# 09_Misc.net
KiCad netlist of a schematic drawn in Altium Designer
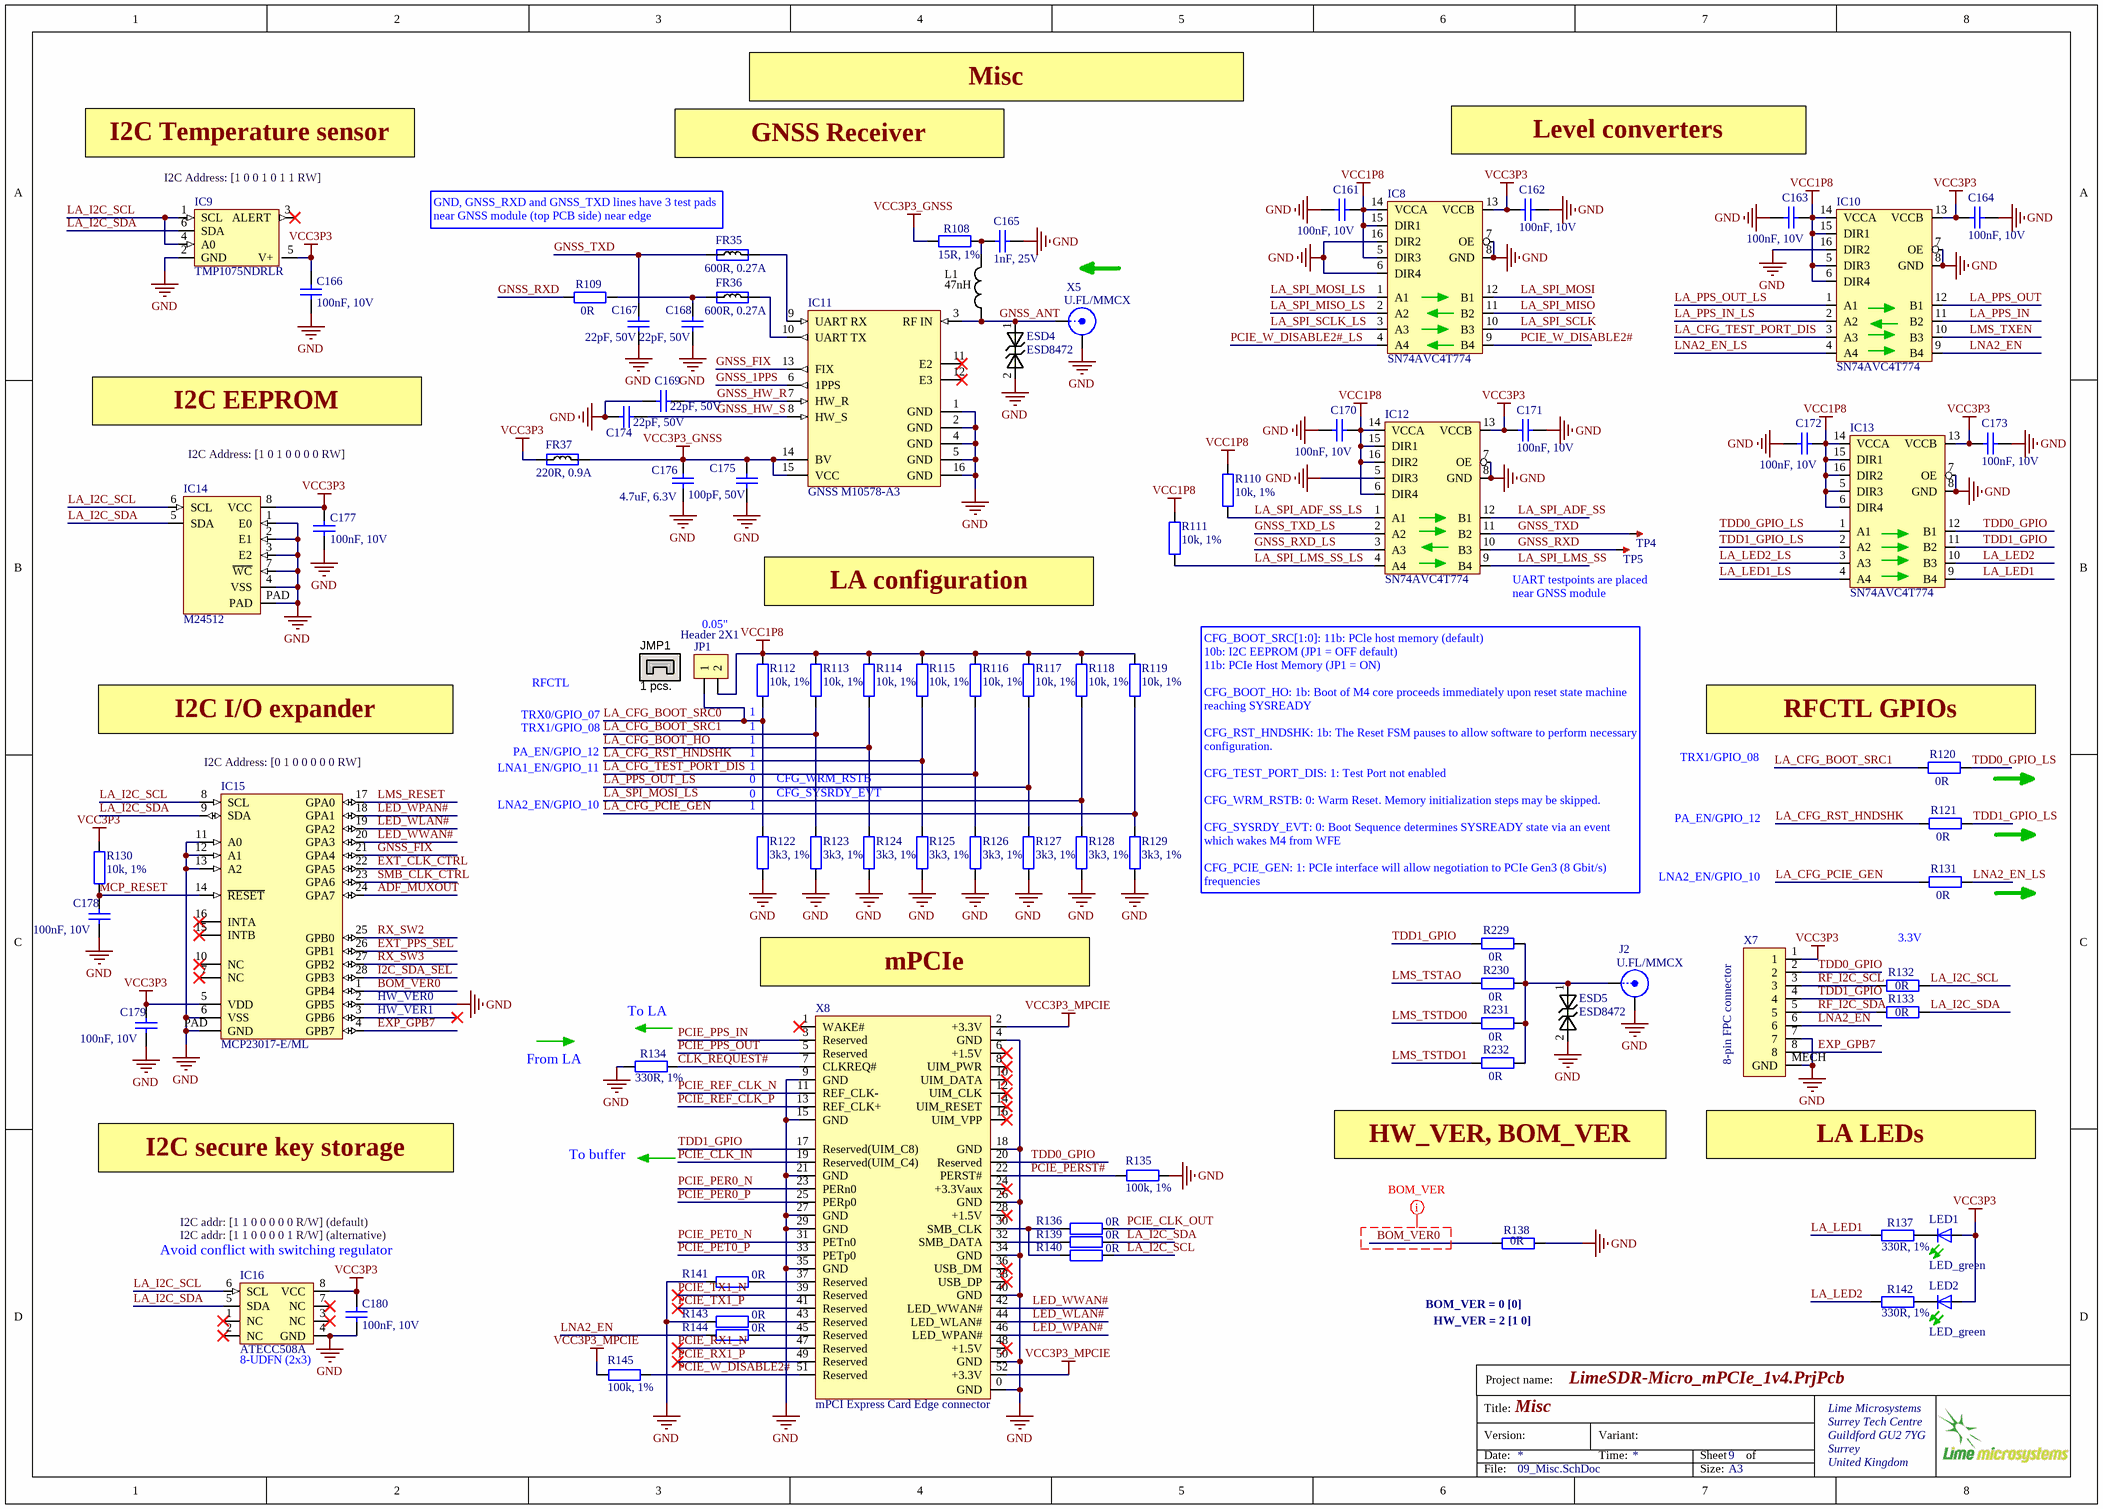
[diagram p0: 09_Misc.SchDoc]

(export (version "E")
  (design (tool "Eeschema 10.0.6"))
  (components
    (comp (ref "C161")
      (value "100nF, 10V")
      (footprint "CAP0201")
      (fields (field (name "MANUFACTURER") "Samsung") (field (name "TOLERANCE") "20%"))
      (libsource (lib "LimeMicroAltiumLib_schLib") (part "Cap_0402"))
    )
    (comp (ref "C162")
      (value "100nF, 10V")
      (footprint "CAP0201")
      (fields (field (name "MANUFACTURER") "Samsung") (field (name "TOLERANCE") "20%"))
      (libsource (lib "LimeMicroAltiumLib_schLib") (part "Cap_0402"))
    )
    (comp (ref "C163")
      (value "100nF, 10V")
      (footprint "CAP0201")
      (fields (field (name "MANUFACTURER") "Samsung") (field (name "TOLERANCE") "20%"))
      (libsource (lib "LimeMicroAltiumLib_schLib") (part "Cap_0402"))
    )
    (comp (ref "C164")
      (value "100nF, 10V")
      (footprint "CAP0201")
      (fields (field (name "MANUFACTURER") "Samsung") (field (name "TOLERANCE") "20%"))
      (libsource (lib "LimeMicroAltiumLib_schLib") (part "Cap_0402"))
    )
    (comp (ref "C165")
      (value "1nF, 25V")
      (footprint "CAP0201")
      (fields (field (name "TOLERANCE") "±10%") (field (name "MANUFACTURER") "TDK Corporation"))
      (libsource (lib "LimeMicroAltiumLib_schLib") (part "Cap_0402"))
    )
    (comp (ref "C166")
      (value "100nF, 10V")
      (footprint "CAP0201")
      (fields (field (name "MANUFACTURER") "Samsung") (field (name "TOLERANCE") "20%"))
      (libsource (lib "LimeMicroAltiumLib_schLib") (part "Cap_0402"))
    )
    (comp (ref "C167")
      (value "22pF, 50V")
      (footprint "CAP0201")
      (fields
        (field (name "MANUFACTURER") "Murata")
        (field (name "TOLERANCE") "5%")
        (field (name "VOLTAGE") "50V")
      )
      (libsource (lib "LimeMicroAltiumLib_schLib") (part "Cap_0402"))
    )
    (comp (ref "C168")
      (value "22pF, 50V")
      (footprint "CAP0201")
      (fields
        (field (name "MANUFACTURER") "Murata")
        (field (name "TOLERANCE") "5%")
        (field (name "VOLTAGE") "50V")
      )
      (libsource (lib "LimeMicroAltiumLib_schLib") (part "Cap_0402"))
    )
    (comp (ref "C169")
      (value "22pF, 50V")
      (footprint "CAP0201")
      (fields
        (field (name "MANUFACTURER") "Murata")
        (field (name "TOLERANCE") "5%")
        (field (name "VOLTAGE") "50V")
      )
      (libsource (lib "LimeMicroAltiumLib_schLib") (part "Cap_0402"))
    )
    (comp (ref "C170")
      (value "100nF, 10V")
      (footprint "CAP0201")
      (fields (field (name "MANUFACTURER") "Samsung") (field (name "TOLERANCE") "20%"))
      (libsource (lib "LimeMicroAltiumLib_schLib") (part "Cap_0402"))
    )
    (comp (ref "C171")
      (value "100nF, 10V")
      (footprint "CAP0201")
      (fields (field (name "MANUFACTURER") "Samsung") (field (name "TOLERANCE") "20%"))
      (libsource (lib "LimeMicroAltiumLib_schLib") (part "Cap_0402"))
    )
    (comp (ref "C172")
      (value "100nF, 10V")
      (footprint "CAP0201")
      (fields (field (name "MANUFACTURER") "Samsung") (field (name "TOLERANCE") "20%"))
      (libsource (lib "LimeMicroAltiumLib_schLib") (part "Cap_0402"))
    )
    (comp (ref "C173")
      (value "100nF, 10V")
      (footprint "CAP0201")
      (fields (field (name "MANUFACTURER") "Samsung") (field (name "TOLERANCE") "20%"))
      (libsource (lib "LimeMicroAltiumLib_schLib") (part "Cap_0402"))
    )
    (comp (ref "C174")
      (value "22pF, 50V")
      (footprint "CAP0201")
      (fields
        (field (name "MANUFACTURER") "Murata")
        (field (name "TOLERANCE") "5%")
        (field (name "VOLTAGE") "50V")
      )
      (libsource (lib "LimeMicroAltiumLib_schLib") (part "Cap_0402"))
    )
    (comp (ref "C175")
      (value "100pF, 50V")
      (footprint "CAP0201")
      (fields
        (field (name "MANUFACTURER") "TDK")
        (field (name "TOLERANCE") "5%")
        (field (name "VOLTAGE") "50V")
      )
      (libsource (lib "LimeMicroAltiumLib_schLib") (part "Cap_0402"))
    )
    (comp (ref "C176")
      (value "4.7uF, 6.3V")
      (footprint "CAP0402")
      (fields
        (field (name "MANUFACTURER") "Murata Electronics North America")
        (field (name "TOLERANCE") "±20%")
      )
      (libsource (lib "LimeMicroAltiumLib_schLib") (part "Cap_0402"))
    )
    (comp (ref "C177")
      (value "100nF, 10V")
      (footprint "CAP0201")
      (fields (field (name "MANUFACTURER") "Samsung") (field (name "TOLERANCE") "20%"))
      (libsource (lib "LimeMicroAltiumLib_schLib") (part "Cap_0402"))
    )
    (comp (ref "C178")
      (value "100nF, 10V")
      (footprint "CAP0201")
      (fields (field (name "MANUFACTURER") "Samsung") (field (name "TOLERANCE") "20%"))
      (libsource (lib "LimeMicroAltiumLib_schLib") (part "Cap_0402"))
    )
    (comp (ref "C179")
      (value "100nF, 10V")
      (footprint "CAP0201")
      (fields (field (name "MANUFACTURER") "Samsung") (field (name "TOLERANCE") "20%"))
      (libsource (lib "LimeMicroAltiumLib_schLib") (part "Cap_0402"))
    )
    (comp (ref "C180")
      (value "100nF, 10V")
      (footprint "CAP0201")
      (fields (field (name "MANUFACTURER") "Samsung") (field (name "TOLERANCE") "20%"))
      (libsource (lib "LimeMicroAltiumLib_schLib") (part "Cap_0402"))
    )
    (comp (ref "ESD4")
      (value "ESD8472")
      (footprint "ESD8472_X3DFN2")
      (fields (field (name "MANUFACTURER") "ON Semiconductor"))
      (libsource (lib "LimeMicroAltiumLib_schLib") (part "ESD8472"))
    )
    (comp (ref "ESD5")
      (value "ESD8472")
      (footprint "ESD8472_X3DFN2")
      (fields (field (name "MANUFACTURER") "ON Semiconductor"))
      (libsource (lib "LimeMicroAltiumLib_schLib") (part "ESD8472"))
    )
    (comp (ref "FR35")
      (value "600R, 0.27A")
      (footprint "RES0201")
      (fields (field (name "MANUFACTURER") "Taiyo Yuden"))
      (libsource (lib "LimeMicroAltiumLib_schLib") (part "Ferrite"))
    )
    (comp (ref "FR36")
      (value "600R, 0.27A")
      (footprint "RES0201")
      (fields (field (name "MANUFACTURER") "Taiyo Yuden"))
      (libsource (lib "LimeMicroAltiumLib_schLib") (part "Ferrite"))
    )
    (comp (ref "FR37")
      (value "220R, 0.9A")
      (footprint "RES0402")
      (fields (field (name "MANUFACTURER") "TDK Corporation"))
      (libsource (lib "LimeFPGAboard_schLib") (part "Ferrite"))
    )
    (comp (ref "IC8")
      (value "SN74AVC4T774")
      (footprint "SN74AVC4T774_v1")
      (fields (field (name "MANUFACTURER") "Texas Instruments"))
      (libsource (lib "LimeMicroAltiumLib") (part "SN74AVC4T774"))
    )
    (comp (ref "IC9")
      (value "TMP1075NDRLR")
      (footprint "TMP1075NDRLR_temperature_sensor_SOT563")
      (fields (field (name "MANUFACTURER") "Texas Instruments"))
      (libsource (lib "LimeMicroAltiumLib_schLib_r04") (part "TMP1075NDRLR_temperature_sensor"))
    )
    (comp (ref "IC10")
      (value "SN74AVC4T774")
      (footprint "SN74AVC4T774_v1")
      (fields (field (name "MANUFACTURER") "Texas Instruments"))
      (libsource (lib "LimeMicroAltiumLib") (part "SN74AVC4T774"))
    )
    (comp (ref "IC11")
      (value "GNSS M10578-A3")
      (footprint "M10578-A3_v2")
      (fields (field (name "MANUFACTURER") "Antenova"))
      (libsource (lib "LimeMicroAltiumLib_schLib_r04") (part "M10578-A3_GPS_GNSS"))
    )
    (comp (ref "IC12")
      (value "SN74AVC4T774")
      (footprint "SN74AVC4T774_v1")
      (fields (field (name "MANUFACTURER") "Texas Instruments"))
      (libsource (lib "LimeMicroAltiumLib") (part "SN74AVC4T774"))
    )
    (comp (ref "IC13")
      (value "SN74AVC4T774")
      (footprint "SN74AVC4T774_v1")
      (fields (field (name "MANUFACTURER") "Texas Instruments"))
      (libsource (lib "LimeMicroAltiumLib") (part "SN74AVC4T774"))
    )
    (comp (ref "IC14")
      (value "M24512")
      (footprint "M24128-DFMC6TG")
      (fields (field (name "MANUFACTURER") "STMicroelectronics"))
      (libsource (lib "LimeMicroAltiumLib_schLib") (part "M24128-DFMC6TG"))
    )
    (comp (ref "IC15")
      (value "MCP23017-E/ML")
      (footprint "MCP23017-E/ML_QFN28")
      (fields (field (name "MANUFACTURER") "Microchip"))
      (libsource (lib "LimeMicroAltiumLib") (part "MCP23017-E/ML_I2C_expander"))
    )
    (comp (ref "IC16")
      (value "ATECC508A")
      (footprint "LimeMicroAltiumLib:ATECC508A_UDFN8_v2")
      (fields (field (name "MANUFACTURER") "Microchip"))
      (libsource (lib "LimeMicroAltiumLib_schLib_r01") (part "ATECC508A_authentication_IC"))
    )
    (comp (ref "J2")
      (value "U.FL/MMCX")
      (footprint "MMCX_UFL_conn_u_v2")
      (description "CONN UMC RCPT STR 50 OHM SMD")
      (fields (field (name "MANUFACTURER") "Molex, LLC"))
      (libsource (lib "LimeMicroAltiumLib_schLib") (part "RF_IF_connector"))
    )
    (comp (ref "JMP1")
      (value "1 pcs.")
      (footprint "MECH_JUMPER_HALF_PITCH")
      (description "Shorting Jumper, 2-position, 1.27mm pitch")
      (fields (field (name "MANUFACTURER") "Sullins"))
      (libsource (lib "LimeMicroAltiumLib_schLib") (part "JUMP_2P_CONN_HEADER"))
    )
    (comp (ref "JP1")
      (value "Header 2X1")
      (footprint "HEADER_2x1_TH_HALF_PITCH")
      (fields (field (name "MANUFACTURER") "Harwin"))
      (libsource (lib "LimeMicroAltiumLib") (part "Header_2X1"))
    )
    (comp (ref "L1")
      (value "47nH")
      (footprint "RES0402")
      (fields
        (field (name "MANUFACTURER") "COILCRAFT")
        (field (name "MANUFACTURER PART NUMBER") "0402HP-47NXJLU")
      )
      (libsource (lib "LimeMicroAltiumLib_schLib") (part "Inductor_0603"))
    )
    (comp (ref "LED1")
      (value "LED_green")
      (footprint "LED0201")
      (fields (field (name "MANUFACTURER") "Kingbright"))
      (libsource (lib "LimeFPGAboard_schLib") (part "LED_green"))
    )
    (comp (ref "LED2")
      (value "LED_green")
      (footprint "LED0201")
      (fields (field (name "MANUFACTURER") "Kingbright"))
      (libsource (lib "LimeFPGAboard_schLib") (part "LED_green"))
    )
    (comp (ref "R108")
      (value "15R, 1%")
      (footprint "RES0201")
      (fields (field (name "MANUFACTURER") "Yageo") (field (name "TOLERANCE") "1%"))
      (libsource (lib "LimeFPGAboard_schLib") (part "Res_0402"))
    )
    (comp (ref "R109")
      (value "0R")
      (footprint "RES0201")
      (fields (field (name "MANUFACTURER") "Yageo") (field (name "TOLERANCE") "5%"))
      (libsource (lib "LimeFPGAboard_schLib") (part "Res_0402"))
    )
    (comp (ref "R110")
      (value "10k, 1%")
      (footprint "RES0201")
      (fields (field (name "MANUFACTURER") "Yageo") (field (name "TOLERANCE") "1%"))
      (libsource (lib "LimeFPGAboard_schLib") (part "Res_0402"))
    )
    (comp (ref "R111")
      (value "10k, 1%")
      (footprint "RES0201")
      (fields (field (name "MANUFACTURER") "Yageo") (field (name "TOLERANCE") "1%"))
      (libsource (lib "LimeFPGAboard_schLib") (part "Res_0402"))
    )
    (comp (ref "R112")
      (value "10k, 1%")
      (footprint "RES0201")
      (fields (field (name "MANUFACTURER") "Yageo") (field (name "TOLERANCE") "1%"))
      (libsource (lib "LimeFPGAboard_schLib") (part "Res_0402"))
    )
    (comp (ref "R113")
      (value "10k, 1%")
      (footprint "RES0201")
      (fields (field (name "MANUFACTURER") "Yageo") (field (name "TOLERANCE") "1%"))
      (libsource (lib "LimeFPGAboard_schLib") (part "Res_0402"))
    )
    (comp (ref "R114")
      (value "10k, 1%")
      (footprint "RES0201")
      (fields (field (name "MANUFACTURER") "Yageo") (field (name "TOLERANCE") "1%"))
      (libsource (lib "LimeFPGAboard_schLib") (part "Res_0402"))
    )
    (comp (ref "R115")
      (value "10k, 1%")
      (footprint "RES0201")
      (fields (field (name "MANUFACTURER") "Yageo") (field (name "TOLERANCE") "1%"))
      (libsource (lib "LimeFPGAboard_schLib") (part "Res_0402"))
    )
    (comp (ref "R116")
      (value "10k, 1%")
      (footprint "RES0201")
      (fields (field (name "MANUFACTURER") "Yageo") (field (name "TOLERANCE") "1%"))
      (libsource (lib "LimeFPGAboard_schLib") (part "Res_0402"))
    )
    (comp (ref "R117")
      (value "10k, 1%")
      (footprint "RES0201")
      (fields (field (name "MANUFACTURER") "Yageo") (field (name "TOLERANCE") "1%"))
      (libsource (lib "LimeFPGAboard_schLib") (part "Res_0402"))
    )
    (comp (ref "R118")
      (value "10k, 1%")
      (footprint "RES0201")
      (fields (field (name "MANUFACTURER") "Yageo") (field (name "TOLERANCE") "1%"))
      (libsource (lib "LimeFPGAboard_schLib") (part "Res_0402"))
    )
    (comp (ref "R119")
      (value "10k, 1%")
      (footprint "RES0201")
      (fields (field (name "MANUFACTURER") "Yageo") (field (name "TOLERANCE") "1%"))
      (libsource (lib "LimeFPGAboard_schLib") (part "Res_0402"))
    )
    (comp (ref "R120")
      (value "0R")
      (footprint "RES0201")
      (fields (field (name "MANUFACTURER") "Yageo") (field (name "TOLERANCE") "5%"))
      (libsource (lib "LimeFPGAboard_schLib") (part "Res_0402"))
    )
    (comp (ref "R121")
      (value "0R")
      (footprint "RES0201")
      (fields (field (name "MANUFACTURER") "Yageo") (field (name "TOLERANCE") "5%"))
      (libsource (lib "LimeFPGAboard_schLib") (part "Res_0402"))
    )
    (comp (ref "R122")
      (value "3k3, 1%")
      (footprint "RES0201")
      (fields (field (name "MANUFACTURER") "Yageo") (field (name "TOLERANCE") "1%"))
      (libsource (lib "LimeFPGAboard_schLib") (part "Res_0402"))
    )
    (comp (ref "R123")
      (value "3k3, 1%")
      (footprint "RES0201")
      (fields (field (name "MANUFACTURER") "Yageo") (field (name "TOLERANCE") "1%"))
      (libsource (lib "LimeFPGAboard_schLib") (part "Res_0402"))
    )
    (comp (ref "R124")
      (value "3k3, 1%")
      (footprint "RES0201")
      (fields (field (name "MANUFACTURER") "Yageo") (field (name "TOLERANCE") "1%"))
      (libsource (lib "LimeFPGAboard_schLib") (part "Res_0402"))
    )
    (comp (ref "R125")
      (value "3k3, 1%")
      (footprint "RES0201")
      (fields (field (name "MANUFACTURER") "Yageo") (field (name "TOLERANCE") "1%"))
      (libsource (lib "LimeFPGAboard_schLib") (part "Res_0402"))
    )
    (comp (ref "R126")
      (value "3k3, 1%")
      (footprint "RES0201")
      (fields (field (name "MANUFACTURER") "Yageo") (field (name "TOLERANCE") "1%"))
      (libsource (lib "LimeFPGAboard_schLib") (part "Res_0402"))
    )
    (comp (ref "R127")
      (value "3k3, 1%")
      (footprint "RES0201")
      (fields (field (name "MANUFACTURER") "Yageo") (field (name "TOLERANCE") "1%"))
      (libsource (lib "LimeFPGAboard_schLib") (part "Res_0402"))
    )
    (comp (ref "R128")
      (value "3k3, 1%")
      (footprint "RES0201")
      (fields (field (name "MANUFACTURER") "Yageo") (field (name "TOLERANCE") "1%"))
      (libsource (lib "LimeFPGAboard_schLib") (part "Res_0402"))
    )
    (comp (ref "R129")
      (value "3k3, 1%")
      (footprint "RES0201")
      (fields (field (name "MANUFACTURER") "Yageo") (field (name "TOLERANCE") "1%"))
      (libsource (lib "LimeFPGAboard_schLib") (part "Res_0402"))
    )
    (comp (ref "R130")
      (value "10k, 1%")
      (footprint "RES0201")
      (fields (field (name "MANUFACTURER") "Yageo") (field (name "TOLERANCE") "1%"))
      (libsource (lib "LimeFPGAboard_schLib") (part "Res_0402"))
    )
    (comp (ref "R131")
      (value "0R")
      (footprint "RES0201")
      (fields (field (name "MANUFACTURER") "Yageo") (field (name "TOLERANCE") "5%"))
      (libsource (lib "LimeFPGAboard_schLib") (part "Res_0402"))
    )
    (comp (ref "R132")
      (value "0R")
      (footprint "RES0201")
      (fields (field (name "MANUFACTURER") "Yageo") (field (name "TOLERANCE") "5%"))
      (libsource (lib "LimeFPGAboard_schLib") (part "Res_0402"))
    )
    (comp (ref "R133")
      (value "0R")
      (footprint "RES0201")
      (fields (field (name "MANUFACTURER") "Yageo") (field (name "TOLERANCE") "5%"))
      (libsource (lib "LimeFPGAboard_schLib") (part "Res_0402"))
    )
    (comp (ref "R134")
      (value "330R, 1%")
      (footprint "RES0201")
      (fields (field (name "MANUFACTURER") "Vishay Dale") (field (name "TOLERANCE") "1%"))
      (libsource (lib "LimeFPGAboard_schLib") (part "Res_0402"))
    )
    (comp (ref "R135")
      (value "100k, 1%")
      (footprint "RES0201")
      (fields (field (name "MANUFACTURER") "Yageo") (field (name "TOLERANCE") "1%"))
      (libsource (lib "LimeMicroAltiumLib_schLib") (part "Res_0402"))
    )
    (comp (ref "R136")
      (value "0R")
      (footprint "RES0201")
      (fields (field (name "MANUFACTURER") "Yageo") (field (name "TOLERANCE") "5%"))
      (libsource (lib "LimeFPGAboard_schLib") (part "Res_0402"))
    )
    (comp (ref "R137")
      (value "330R, 1%")
      (footprint "RES0201")
      (fields (field (name "MANUFACTURER") "Vishay Dale") (field (name "TOLERANCE") "1%"))
      (libsource (lib "LimeFPGAboard_schLib") (part "Res_0402"))
    )
    (comp (ref "R138")
      (value "0R")
      (footprint "RES0201")
      (fields (field (name "MANUFACTURER") "Yageo") (field (name "TOLERANCE") "5%"))
      (libsource (lib "LimeFPGAboard_schLib") (part "Res_0402"))
    )
    (comp (ref "R139")
      (value "0R")
      (footprint "RES0201")
      (fields (field (name "MANUFACTURER") "Yageo") (field (name "TOLERANCE") "5%"))
      (libsource (lib "LimeFPGAboard_schLib") (part "Res_0402"))
    )
    (comp (ref "R140")
      (value "0R")
      (footprint "RES0201")
      (fields (field (name "MANUFACTURER") "Yageo") (field (name "TOLERANCE") "5%"))
      (libsource (lib "LimeFPGAboard_schLib") (part "Res_0402"))
    )
    (comp (ref "R141")
      (value "0R")
      (footprint "RES0201")
      (fields (field (name "MANUFACTURER") "Yageo") (field (name "TOLERANCE") "5%"))
      (libsource (lib "LimeFPGAboard_schLib") (part "Res_0402"))
    )
    (comp (ref "R142")
      (value "330R, 1%")
      (footprint "RES0201")
      (fields (field (name "MANUFACTURER") "Vishay Dale") (field (name "TOLERANCE") "1%"))
      (libsource (lib "LimeFPGAboard_schLib") (part "Res_0402"))
    )
    (comp (ref "R143")
      (value "0R")
      (footprint "RES0201")
      (fields (field (name "MANUFACTURER") "Yageo") (field (name "TOLERANCE") "5%"))
      (libsource (lib "LimeFPGAboard_schLib") (part "Res_0402"))
    )
    (comp (ref "R144")
      (value "0R")
      (footprint "RES0201")
      (fields (field (name "MANUFACTURER") "Yageo") (field (name "TOLERANCE") "5%"))
      (libsource (lib "LimeFPGAboard_schLib") (part "Res_0402"))
    )
    (comp (ref "R145")
      (value "100k, 1%")
      (footprint "RES0201")
      (fields (field (name "MANUFACTURER") "Yageo") (field (name "TOLERANCE") "1%"))
      (libsource (lib "LimeMicroAltiumLib_schLib") (part "Res_0402"))
    )
    (comp (ref "R229")
      (value "0R")
      (footprint "RES0201")
      (fields (field (name "MANUFACTURER") "Yageo") (field (name "TOLERANCE") "5%"))
      (libsource (lib "LimeFPGAboard_schLib") (part "Res_0402"))
    )
    (comp (ref "R230")
      (value "0R")
      (footprint "RES0201")
      (fields (field (name "MANUFACTURER") "Yageo") (field (name "TOLERANCE") "5%"))
      (libsource (lib "LimeFPGAboard_schLib") (part "Res_0402"))
    )
    (comp (ref "R231")
      (value "0R")
      (footprint "RES0201")
      (fields (field (name "MANUFACTURER") "Yageo") (field (name "TOLERANCE") "5%"))
      (libsource (lib "LimeFPGAboard_schLib") (part "Res_0402"))
    )
    (comp (ref "R232")
      (value "0R")
      (footprint "RES0201")
      (fields (field (name "MANUFACTURER") "Yageo") (field (name "TOLERANCE") "5%"))
      (libsource (lib "LimeFPGAboard_schLib") (part "Res_0402"))
    )
    (comp (ref "TP4")
      (value "TESTPOINT_PAD")
      (footprint "TP_PAD_1MM")
      (description "Test Point PCB mount Miniature White")
      (libsource (lib "LimeMicroAltiumLib_schLib_r04") (part "TESTPOINT_PAD"))
    )
    (comp (ref "TP5")
      (value "TESTPOINT_PAD")
      (footprint "TP_PAD_1MM")
      (description "Test Point PCB mount Miniature White")
      (libsource (lib "LimeMicroAltiumLib_schLib_r04") (part "TESTPOINT_PAD"))
    )
    (comp (ref "X5")
      (value "U.FL/MMCX")
      (footprint "MMCX_UFL_conn_u_v2")
      (description "CONN UMC RCPT STR 50 OHM SMD")
      (fields (field (name "MANUFACTURER") "Molex, LLC"))
      (libsource (lib "LimeMicroAltiumLib_schLib") (part "RF_IF_connector"))
    )
    (comp (ref "X7")
      (value "8-pin FPC connector")
      (footprint "503480-0800_8PIN_FPC_CONN")
      (fields (field (name "MANUFACTURER") "Molex"))
      (libsource (lib "LimeMicroAltiumLib_schLib_r04") (part "503480-0800_8PIN_FPC_CONN"))
    )
    (comp (ref "X8")
      (value "mPCI Express Card Edge connector")
      (footprint "PCIe_MiniCard")
      (description "PCIe MiniCard full or half size")
      (libsource (lib "LimeMicroAltiumLib_schLib_r04") (part "PCIe_MiniCard_fingers"))
    )
  )
  (nets
    (net (code "1") (name "/ADF_MUXOUT") (class "Default")
      (node (ref "IC15") (pin "24") (pinfunction "GPA7_24") (pintype "bidirectional"))
    )
    (net (code "2") (name "/BOM_VER0") (class "Default")
      (node (ref "IC15") (pin "1") (pinfunction "GPB4_1") (pintype "bidirectional"))
      (node (ref "R138") (pin "1") (pinfunction "1_1") (pintype "passive"))
    )
    (net (code "3") (name "/CLK_REQUEST#") (class "Default")
      (node (ref "R134") (pin "1") (pinfunction "1_1") (pintype "passive"))
      (node (ref "X8") (pin "7") (pinfunction "CLKREQ#_7") (pintype "passive"))
    )
    (net (code "4") (name "/EXP_GPB7") (class "Default")
      (node (ref "IC15") (pin "4") (pinfunction "GPB7_4") (pintype "bidirectional"))
      (node (ref "X7") (pin "8") (pinfunction "8_8") (pintype "passive"))
    )
    (net (code "5") (name "/EXT_CLK_CTRL") (class "Default")
      (node (ref "IC15") (pin "22") (pinfunction "GPA5_22") (pintype "bidirectional"))
    )
    (net (code "6") (name "/EXT_PPS_SEL") (class "Default")
      (node (ref "IC15") (pin "26") (pinfunction "GPB1_26") (pintype "bidirectional"))
    )
    (net (code "7") (name "/GNSS_1PPS") (class "Default")
      (node (ref "IC11") (pin "6") (pinfunction "1PPS_6") (pintype "output"))
    )
    (net (code "8") (name "/GNSS_ANT") (class "Default")
      (node (ref "ESD4") (pin "1") (pinfunction "1_1") (pintype "passive"))
      (node (ref "IC11") (pin "3") (pinfunction "RF_IN_3") (pintype "input"))
      (node (ref "L1") (pin "1") (pinfunction "1_1") (pintype "passive"))
      (node (ref "X5") (pin "1") (pinfunction "X_1") (pintype "passive"))
    )
    (net (code "9") (name "/GNSS_FIX") (class "Default")
      (node (ref "IC11") (pin "13") (pinfunction "FIX_13") (pintype "output"))
      (node (ref "IC15") (pin "21") (pinfunction "GPA4_21") (pintype "bidirectional"))
    )
    (net (code "10") (name "/GNSS_HW_R") (class "Default")
      (node (ref "C169") (pin "1") (pinfunction "1_1") (pintype "passive"))
      (node (ref "IC11") (pin "7") (pinfunction "HW_R_7") (pintype "input"))
    )
    (net (code "11") (name "/GNSS_HW_S") (class "Default")
      (node (ref "C174") (pin "1") (pinfunction "1_1") (pintype "passive"))
      (node (ref "IC11") (pin "8") (pinfunction "HW_S_8") (pintype "input"))
    )
    (net (code "12") (name "/GNSS_RXD") (class "Default")
      (node (ref "IC12") (pin "10") (pinfunction "B3_10") (pintype "passive"))
      (node (ref "R109") (pin "1") (pinfunction "1_1") (pintype "passive"))
      (node (ref "TP5") (pin "1") (pintype "passive"))
    )
    (net (code "13") (name "/GNSS_RXD_LS") (class "Default")
      (node (ref "IC12") (pin "3") (pinfunction "A3_3") (pintype "passive"))
    )
    (net (code "14") (name "/GNSS_TXD") (class "Default")
      (node (ref "C167") (pin "1") (pinfunction "1_1") (pintype "passive"))
      (node (ref "FR35") (pin "1") (pinfunction "1_1") (pintype "passive"))
      (node (ref "IC12") (pin "11") (pinfunction "B2_11") (pintype "passive"))
      (node (ref "TP4") (pin "1") (pintype "passive"))
    )
    (net (code "15") (name "/GNSS_TXD_LS") (class "Default")
      (node (ref "IC12") (pin "2") (pinfunction "A2_2") (pintype "passive"))
    )
    (net (code "16") (name "/I2C_SDA_SEL") (class "Default")
      (node (ref "IC15") (pin "28") (pinfunction "GPB3_28") (pintype "bidirectional"))
    )
    (net (code "17") (name "/LA_CFG_BOOT_HO") (class "Default")
      (node (ref "R114") (pin "2") (pinfunction "2_2") (pintype "passive"))
      (node (ref "R124") (pin "1") (pinfunction "1_1") (pintype "passive"))
    )
    (net (code "18") (name "/LA_CFG_BOOT_SRC0") (class "Default")
      (node (ref "JP1") (pin "1") (pinfunction "1_1") (pintype "passive"))
      (node (ref "R112") (pin "2") (pinfunction "2_2") (pintype "passive"))
      (node (ref "R122") (pin "1") (pinfunction "1_1") (pintype "passive"))
    )
    (net (code "19") (name "/LA_CFG_BOOT_SRC1") (class "Default")
      (node (ref "R113") (pin "2") (pinfunction "2_2") (pintype "passive"))
      (node (ref "R120") (pin "1") (pinfunction "1_1") (pintype "passive"))
      (node (ref "R123") (pin "1") (pinfunction "1_1") (pintype "passive"))
    )
    (net (code "20") (name "/LA_CFG_PCIE_GEN") (class "Default")
      (node (ref "R119") (pin "2") (pinfunction "2_2") (pintype "passive"))
      (node (ref "R129") (pin "1") (pinfunction "1_1") (pintype "passive"))
      (node (ref "R131") (pin "1") (pinfunction "1_1") (pintype "passive"))
    )
    (net (code "21") (name "/LA_CFG_RST_HNDSHK") (class "Default")
      (node (ref "R115") (pin "2") (pinfunction "2_2") (pintype "passive"))
      (node (ref "R121") (pin "1") (pinfunction "1_1") (pintype "passive"))
      (node (ref "R125") (pin "1") (pinfunction "1_1") (pintype "passive"))
    )
    (net (code "22") (name "/LA_CFG_TEST_PORT_DIS") (class "Default")
      (node (ref "IC10") (pin "3") (pinfunction "A3_3") (pintype "passive"))
      (node (ref "R116") (pin "2") (pinfunction "2_2") (pintype "passive"))
      (node (ref "R126") (pin "1") (pinfunction "1_1") (pintype "passive"))
    )
    (net (code "23") (name "/LA_I2C_SCL") (class "Default")
      (node (ref "IC14") (pin "6") (pinfunction "SCL_6") (pintype "input"))
      (node (ref "IC15") (pin "8") (pinfunction "SCL_8") (pintype "input"))
      (node (ref "IC16") (pin "6") (pinfunction "SCL_6") (pintype "input"))
      (node (ref "IC9") (pin "1") (pinfunction "SCL_1") (pintype "input"))
      (node (ref "IC9") (pin "4") (pinfunction "A0_4") (pintype "input"))
      (node (ref "R132") (pin "2") (pinfunction "2_2") (pintype "passive"))
      (node (ref "R140") (pin "2") (pinfunction "2_2") (pintype "passive"))
    )
    (net (code "24") (name "/LA_I2C_SDA") (class "Default")
      (node (ref "IC14") (pin "5") (pinfunction "SDA_5") (pintype "bidirectional"))
      (node (ref "IC15") (pin "9") (pinfunction "SDA_9") (pintype "bidirectional"))
      (node (ref "IC16") (pin "5") (pinfunction "SDA_5") (pintype "bidirectional"))
      (node (ref "IC9") (pin "6") (pinfunction "SDA_6") (pintype "bidirectional"))
      (node (ref "R133") (pin "2") (pinfunction "2_2") (pintype "passive"))
      (node (ref "R139") (pin "2") (pinfunction "2_2") (pintype "passive"))
    )
    (net (code "25") (name "/LA_LED1") (class "Default")
      (node (ref "IC13") (pin "9") (pinfunction "B4_9") (pintype "passive"))
      (node (ref "R137") (pin "2") (pinfunction "2_2") (pintype "passive"))
    )
    (net (code "26") (name "/LA_LED1_LS") (class "Default")
      (node (ref "IC13") (pin "4") (pinfunction "A4_4") (pintype "passive"))
    )
    (net (code "27") (name "/LA_LED2") (class "Default")
      (node (ref "IC13") (pin "10") (pinfunction "B3_10") (pintype "passive"))
      (node (ref "R142") (pin "2") (pinfunction "2_2") (pintype "passive"))
    )
    (net (code "28") (name "/LA_LED2_LS") (class "Default")
      (node (ref "IC13") (pin "3") (pinfunction "A3_3") (pintype "passive"))
    )
    (net (code "29") (name "/LA_PPS_IN") (class "Default")
      (node (ref "IC10") (pin "11") (pinfunction "B2_11") (pintype "passive"))
    )
    (net (code "30") (name "/LA_PPS_IN_LS") (class "Default")
      (node (ref "IC10") (pin "2") (pinfunction "A2_2") (pintype "passive"))
    )
    (net (code "31") (name "/LA_PPS_OUT") (class "Default")
      (node (ref "IC10") (pin "12") (pinfunction "B1_12") (pintype "passive"))
    )
    (net (code "32") (name "/LA_PPS_OUT_LS") (class "Default")
      (node (ref "IC10") (pin "1") (pinfunction "A1_1") (pintype "passive"))
      (node (ref "R117") (pin "2") (pinfunction "2_2") (pintype "passive"))
      (node (ref "R127") (pin "1") (pinfunction "1_1") (pintype "passive"))
    )
    (net (code "33") (name "/LA_SPI_ADF_SS") (class "Default")
      (node (ref "IC12") (pin "12") (pinfunction "B1_12") (pintype "passive"))
    )
    (net (code "34") (name "/LA_SPI_ADF_SS_LS") (class "Default")
      (node (ref "IC12") (pin "1") (pinfunction "A1_1") (pintype "passive"))
      (node (ref "R110") (pin "2") (pinfunction "2_2") (pintype "passive"))
    )
    (net (code "35") (name "/LA_SPI_LMS_SS") (class "Default")
      (node (ref "IC12") (pin "9") (pinfunction "B4_9") (pintype "passive"))
    )
    (net (code "36") (name "/LA_SPI_LMS_SS_LS") (class "Default")
      (node (ref "IC12") (pin "4") (pinfunction "A4_4") (pintype "passive"))
      (node (ref "R111") (pin "2") (pinfunction "2_2") (pintype "passive"))
    )
    (net (code "37") (name "/LA_SPI_MISO") (class "Default")
      (node (ref "IC8") (pin "11") (pinfunction "B2_11") (pintype "passive"))
    )
    (net (code "38") (name "/LA_SPI_MISO_LS") (class "Default")
      (node (ref "IC8") (pin "2") (pinfunction "A2_2") (pintype "passive"))
    )
    (net (code "39") (name "/LA_SPI_MOSI") (class "Default")
      (node (ref "IC8") (pin "12") (pinfunction "B1_12") (pintype "passive"))
    )
    (net (code "40") (name "/LA_SPI_MOSI_LS") (class "Default")
      (node (ref "IC8") (pin "1") (pinfunction "A1_1") (pintype "passive"))
      (node (ref "R118") (pin "2") (pinfunction "2_2") (pintype "passive"))
      (node (ref "R128") (pin "1") (pinfunction "1_1") (pintype "passive"))
    )
    (net (code "41") (name "/LA_SPI_SCLK") (class "Default")
      (node (ref "IC8") (pin "10") (pinfunction "B3_10") (pintype "passive"))
    )
    (net (code "42") (name "/LA_SPI_SCLK_LS") (class "Default")
      (node (ref "IC8") (pin "3") (pinfunction "A3_3") (pintype "passive"))
    )
    (net (code "43") (name "/LED_WLAN#") (class "Default")
      (node (ref "IC15") (pin "19") (pinfunction "GPA2_19") (pintype "bidirectional"))
      (node (ref "X8") (pin "44") (pinfunction "LED_WLAN#_44") (pintype "passive"))
    )
    (net (code "44") (name "/LED_WPAN#") (class "Default")
      (node (ref "IC15") (pin "18") (pinfunction "GPA1_18") (pintype "bidirectional"))
      (node (ref "X8") (pin "46") (pinfunction "LED_WPAN#_46") (pintype "passive"))
    )
    (net (code "45") (name "/LED_WWAN#") (class "Default")
      (node (ref "IC15") (pin "20") (pinfunction "GPA3_20") (pintype "bidirectional"))
      (node (ref "X8") (pin "42") (pinfunction "LED_WWAN#_42") (pintype "passive"))
    )
    (net (code "46") (name "/LMS_RESET") (class "Default")
      (node (ref "IC15") (pin "17") (pinfunction "GPA0_17") (pintype "bidirectional"))
    )
    (net (code "47") (name "/LMS_TSTAO") (class "Default")
      (node (ref "R230") (pin "1") (pinfunction "1_1") (pintype "passive"))
    )
    (net (code "48") (name "/LMS_TSTDO0") (class "Default")
      (node (ref "R231") (pin "1") (pinfunction "1_1") (pintype "passive"))
    )
    (net (code "49") (name "/LMS_TSTDO1") (class "Default")
      (node (ref "R232") (pin "1") (pinfunction "1_1") (pintype "passive"))
    )
    (net (code "50") (name "/LMS_TXEN") (class "Default")
      (node (ref "IC10") (pin "10") (pinfunction "B3_10") (pintype "passive"))
    )
    (net (code "51") (name "/LNA2_EN") (class "Default")
      (node (ref "IC10") (pin "9") (pinfunction "B4_9") (pintype "passive"))
      (node (ref "R144") (pin "1") (pinfunction "1_1") (pintype "passive"))
      (node (ref "X7") (pin "6") (pinfunction "6_6") (pintype "passive"))
    )
    (net (code "52") (name "/LNA2_EN_LS") (class "Default")
      (node (ref "IC10") (pin "4") (pinfunction "A4_4") (pintype "passive"))
      (node (ref "R131") (pin "2") (pinfunction "2_2") (pintype "passive"))
    )
    (net (code "53") (name "/MCP_RESET") (class "Default")
      (node (ref "C178") (pin "1") (pinfunction "1_1") (pintype "passive"))
      (node (ref "IC15") (pin "14") (pinfunction "~{RESET}_14") (pintype "input"))
      (node (ref "R130") (pin "2") (pinfunction "2_2") (pintype "passive"))
    )
    (net (code "54") (name "/PCIE_CLK_IN") (class "Default")
      (node (ref "X8") (pin "19") (pinfunction "Reserved(UIM_C4)_19") (pintype "passive"))
    )
    (net (code "55") (name "/PCIE_CLK_OUT") (class "Default")
      (node (ref "R136") (pin "2") (pinfunction "2_2") (pintype "passive"))
    )
    (net (code "56") (name "/PCIE_PER0_N") (class "Default")
      (node (ref "X8") (pin "23") (pinfunction "PERn0_23") (pintype "passive"))
    )
    (net (code "57") (name "/PCIE_PER0_P") (class "Default")
      (node (ref "X8") (pin "25") (pinfunction "PERp0_25") (pintype "passive"))
    )
    (net (code "58") (name "/PCIE_PERST#") (class "Default")
      (node (ref "R135") (pin "2") (pinfunction "2_2") (pintype "passive"))
      (node (ref "X8") (pin "22") (pinfunction "PERST#_22") (pintype "passive"))
    )
    (net (code "59") (name "/PCIE_PET0_N") (class "Default")
      (node (ref "X8") (pin "31") (pinfunction "PETn0_31") (pintype "passive"))
    )
    (net (code "60") (name "/PCIE_PET0_P") (class "Default")
      (node (ref "X8") (pin "33") (pinfunction "PETp0_33") (pintype "passive"))
    )
    (net (code "61") (name "/PCIE_PPS_IN") (class "Default")
      (node (ref "X8") (pin "3") (pinfunction "Reserved_3") (pintype "passive"))
    )
    (net (code "62") (name "/PCIE_PPS_OUT") (class "Default")
      (node (ref "X8") (pin "5") (pinfunction "Reserved_5") (pintype "passive"))
    )
    (net (code "63") (name "/PCIE_REF_CLK_N") (class "Default")
      (node (ref "X8") (pin "11") (pinfunction "REF_CLK-_11") (pintype "passive"))
    )
    (net (code "64") (name "/PCIE_REF_CLK_P") (class "Default")
      (node (ref "X8") (pin "13") (pinfunction "REF_CLK+_13") (pintype "passive"))
    )
    (net (code "65") (name "/PCIE_RX1_N") (class "Default")
      (node (ref "X8") (pin "47") (pinfunction "Reserved_47") (pintype "passive+no_connect"))
    )
    (net (code "66") (name "/PCIE_RX1_P") (class "Default")
      (node (ref "X8") (pin "49") (pinfunction "Reserved_49") (pintype "passive+no_connect"))
    )
    (net (code "67") (name "/PCIE_TX1_N") (class "Default")
      (node (ref "X8") (pin "39") (pinfunction "Reserved_39") (pintype "passive+no_connect"))
    )
    (net (code "68") (name "/PCIE_TX1_P") (class "Default")
      (node (ref "X8") (pin "41") (pinfunction "Reserved_41") (pintype "passive+no_connect"))
    )
    (net (code "69") (name "/PCIE_W_DISABLE2#") (class "Default")
      (node (ref "IC8") (pin "9") (pinfunction "B4_9") (pintype "passive"))
      (node (ref "R145") (pin "1") (pinfunction "1_1") (pintype "passive"))
      (node (ref "X8") (pin "51") (pinfunction "Reserved_51") (pintype "passive"))
    )
    (net (code "70") (name "/PCIE_W_DISABLE2#_LS") (class "Default")
      (node (ref "IC8") (pin "4") (pinfunction "A4_4") (pintype "passive"))
    )
    (net (code "71") (name "/RF_I2C_SCL") (class "Default")
      (node (ref "R132") (pin "1") (pinfunction "1_1") (pintype "passive"))
      (node (ref "X7") (pin "3") (pinfunction "3_3") (pintype "passive"))
    )
    (net (code "72") (name "/RF_I2C_SDA") (class "Default")
      (node (ref "R133") (pin "1") (pinfunction "1_1") (pintype "passive"))
      (node (ref "X7") (pin "5") (pinfunction "5_5") (pintype "passive"))
    )
    (net (code "73") (name "/RX_SW2") (class "Default")
      (node (ref "IC15") (pin "25") (pinfunction "GPB0_25") (pintype "bidirectional"))
    )
    (net (code "74") (name "/RX_SW3") (class "Default")
      (node (ref "IC15") (pin "27") (pinfunction "GPB2_27") (pintype "bidirectional"))
    )
    (net (code "75") (name "/SMB_CLK_CTRL") (class "Default")
      (node (ref "IC15") (pin "23") (pinfunction "GPA6_23") (pintype "bidirectional"))
    )
    (net (code "76") (name "/TDD0_GPIO") (class "Default")
      (node (ref "IC13") (pin "12") (pinfunction "B1_12") (pintype "passive"))
      (node (ref "X7") (pin "2") (pinfunction "2_2") (pintype "passive"))
      (node (ref "X8") (pin "20") (pinfunction "Reserved_20") (pintype "passive"))
    )
    (net (code "77") (name "/TDD0_GPIO_LS") (class "Default")
      (node (ref "IC13") (pin "1") (pinfunction "A1_1") (pintype "passive"))
      (node (ref "R120") (pin "2") (pinfunction "2_2") (pintype "passive"))
    )
    (net (code "78") (name "/TDD1_GPIO") (class "Default")
      (node (ref "IC13") (pin "11") (pinfunction "B2_11") (pintype "passive"))
      (node (ref "R229") (pin "1") (pinfunction "1_1") (pintype "passive"))
      (node (ref "X7") (pin "4") (pinfunction "4_4") (pintype "passive"))
      (node (ref "X8") (pin "17") (pinfunction "Reserved(UIM_C8)_17") (pintype "passive"))
    )
    (net (code "79") (name "/TDD1_GPIO_LS") (class "Default")
      (node (ref "IC13") (pin "2") (pinfunction "A2_2") (pintype "passive"))
      (node (ref "R121") (pin "2") (pinfunction "2_2") (pintype "passive"))
    )
    (net (code "80") (name "GND") (class "Default")
      (node (ref "C161") (pin "1") (pinfunction "1_1") (pintype "passive"))
      (node (ref "C162") (pin "2") (pinfunction "2_2") (pintype "passive"))
      (node (ref "C163") (pin "1") (pinfunction "1_1") (pintype "passive"))
      (node (ref "C164") (pin "2") (pinfunction "2_2") (pintype "passive"))
      (node (ref "C165") (pin "2") (pinfunction "2_2") (pintype "passive"))
      (node (ref "C166") (pin "2") (pinfunction "2_2") (pintype "passive"))
      (node (ref "C167") (pin "2") (pinfunction "2_2") (pintype "passive"))
      (node (ref "C168") (pin "2") (pinfunction "2_2") (pintype "passive"))
      (node (ref "C169") (pin "2") (pinfunction "2_2") (pintype "passive"))
      (node (ref "C170") (pin "1") (pinfunction "1_1") (pintype "passive"))
      (node (ref "C171") (pin "2") (pinfunction "2_2") (pintype "passive"))
      (node (ref "C172") (pin "1") (pinfunction "1_1") (pintype "passive"))
      (node (ref "C173") (pin "2") (pinfunction "2_2") (pintype "passive"))
      (node (ref "C174") (pin "2") (pinfunction "2_2") (pintype "passive"))
      (node (ref "C175") (pin "1") (pinfunction "1_1") (pintype "passive"))
      (node (ref "C176") (pin "1") (pinfunction "1_1") (pintype "passive"))
      (node (ref "C177") (pin "2") (pinfunction "2_2") (pintype "passive"))
      (node (ref "C178") (pin "2") (pinfunction "2_2") (pintype "passive"))
      (node (ref "C179") (pin "2") (pinfunction "2_2") (pintype "passive"))
      (node (ref "C180") (pin "2") (pinfunction "2_2") (pintype "passive"))
      (node (ref "ESD4") (pin "2") (pinfunction "2_2") (pintype "passive"))
      (node (ref "ESD5") (pin "2") (pinfunction "2_2") (pintype "passive"))
      (node (ref "IC10") (pin "16") (pinfunction "DIR2_16") (pintype "passive"))
      (node (ref "IC10") (pin "7") (pinfunction "OE_7") (pintype "passive"))
      (node (ref "IC10") (pin "8") (pinfunction "GND_8") (pintype "passive"))
      (node (ref "IC11") (pin "1") (pinfunction "GND_1") (pintype "passive"))
      (node (ref "IC11") (pin "16") (pinfunction "GND_16") (pintype "passive"))
      (node (ref "IC11") (pin "2") (pinfunction "GND_2") (pintype "passive"))
      (node (ref "IC11") (pin "4") (pinfunction "GND_4") (pintype "passive"))
      (node (ref "IC11") (pin "5") (pinfunction "GND_5") (pintype "passive"))
      (node (ref "IC12") (pin "5") (pinfunction "DIR3_5") (pintype "passive"))
      (node (ref "IC12") (pin "7") (pinfunction "OE_7") (pintype "passive"))
      (node (ref "IC12") (pin "8") (pinfunction "GND_8") (pintype "passive"))
      (node (ref "IC13") (pin "7") (pinfunction "OE_7") (pintype "passive"))
      (node (ref "IC13") (pin "8") (pinfunction "GND_8") (pintype "passive"))
      (node (ref "IC14") (pin "1") (pinfunction "E0_1") (pintype "input"))
      (node (ref "IC14") (pin "2") (pinfunction "E1_2") (pintype "input"))
      (node (ref "IC14") (pin "3") (pinfunction "E2_3") (pintype "input"))
      (node (ref "IC14") (pin "4") (pinfunction "VSS_4") (pintype "power_in"))
      (node (ref "IC14") (pin "7") (pinfunction "~{WC}_7") (pintype "input"))
      (node (ref "IC14") (pin "PAD") (pinfunction "PAD_PAD") (pintype "power_in"))
      (node (ref "IC15") (pin "11") (pinfunction "A0_11") (pintype "input"))
      (node (ref "IC15") (pin "12") (pinfunction "A1_12") (pintype "input"))
      (node (ref "IC15") (pin "13") (pinfunction "A2_13") (pintype "input"))
      (node (ref "IC15") (pin "2") (pinfunction "GPB5_2") (pintype "bidirectional"))
      (node (ref "IC15") (pin "6") (pinfunction "VSS_6") (pintype "power_in"))
      (node (ref "IC15") (pin "PAD") (pinfunction "GND_PAD") (pintype "passive"))
      (node (ref "IC16") (pin "4") (pinfunction "GND_4") (pintype "passive"))
      (node (ref "IC8") (pin "16") (pinfunction "DIR2_16") (pintype "passive"))
      (node (ref "IC8") (pin "6") (pinfunction "DIR4_6") (pintype "passive"))
      (node (ref "IC8") (pin "7") (pinfunction "OE_7") (pintype "passive"))
      (node (ref "IC8") (pin "8") (pinfunction "GND_8") (pintype "passive"))
      (node (ref "IC9") (pin "2") (pinfunction "GND_2") (pintype "passive"))
      (node (ref "J2") (pin "2") (pinfunction "Y_2") (pintype "passive"))
      (node (ref "R122") (pin "2") (pinfunction "2_2") (pintype "passive"))
      (node (ref "R123") (pin "2") (pinfunction "2_2") (pintype "passive"))
      (node (ref "R124") (pin "2") (pinfunction "2_2") (pintype "passive"))
      (node (ref "R125") (pin "2") (pinfunction "2_2") (pintype "passive"))
      (node (ref "R126") (pin "2") (pinfunction "2_2") (pintype "passive"))
      (node (ref "R127") (pin "2") (pinfunction "2_2") (pintype "passive"))
      (node (ref "R128") (pin "2") (pinfunction "2_2") (pintype "passive"))
      (node (ref "R129") (pin "2") (pinfunction "2_2") (pintype "passive"))
      (node (ref "R134") (pin "2") (pinfunction "2_2") (pintype "passive"))
      (node (ref "R135") (pin "1") (pinfunction "1_1") (pintype "passive"))
      (node (ref "R138") (pin "2") (pinfunction "2_2") (pintype "passive"))
      (node (ref "R141") (pin "1") (pinfunction "1_1") (pintype "passive"))
      (node (ref "R143") (pin "1") (pinfunction "1_1") (pintype "passive"))
      (node (ref "X5") (pin "2") (pinfunction "Y_2") (pintype "passive"))
      (node (ref "X7") (pin "7") (pinfunction "7_7") (pintype "passive"))
      (node (ref "X7") (pin "MECH") (pinfunction "GND_MECH") (pintype "passive"))
      (node (ref "X8") (pin "0") (pinfunction "GND_0") (pintype "passive"))
      (node (ref "X8") (pin "15") (pinfunction "GND_15") (pintype "passive"))
      (node (ref "X8") (pin "18") (pinfunction "GND_18") (pintype "passive"))
      (node (ref "X8") (pin "21") (pinfunction "GND_21") (pintype "passive"))
      (node (ref "X8") (pin "26") (pinfunction "GND_26") (pintype "passive"))
      (node (ref "X8") (pin "27") (pinfunction "GND_27") (pintype "passive"))
      (node (ref "X8") (pin "29") (pinfunction "GND_29") (pintype "passive"))
      (node (ref "X8") (pin "34") (pinfunction "GND_34") (pintype "passive"))
      (node (ref "X8") (pin "35") (pinfunction "GND_35") (pintype "passive"))
      (node (ref "X8") (pin "4") (pinfunction "GND_4") (pintype "passive"))
      (node (ref "X8") (pin "40") (pinfunction "GND_40") (pintype "passive"))
      (node (ref "X8") (pin "50") (pinfunction "GND_50") (pintype "passive"))
      (node (ref "X8") (pin "9") (pinfunction "GND_9") (pintype "passive"))
    )
    (net (code "81") (name "Net-(C165-Pad1)") (class "Default")
      (node (ref "C165") (pin "1") (pinfunction "1_1") (pintype "passive"))
      (node (ref "L1") (pin "2") (pinfunction "2_2") (pintype "passive"))
      (node (ref "R108") (pin "1") (pinfunction "1_1") (pintype "passive"))
    )
    (net (code "82") (name "Net-(C168-Pad1)") (class "Default")
      (node (ref "C168") (pin "1") (pinfunction "1_1") (pintype "passive"))
      (node (ref "FR36") (pin "1") (pinfunction "1_1") (pintype "passive"))
      (node (ref "R109") (pin "2") (pinfunction "2_2") (pintype "passive"))
    )
    (net (code "83") (name "Net-(IC11-UART_RX)") (class "Default")
      (node (ref "FR35") (pin "2") (pinfunction "2_2") (pintype "passive"))
      (node (ref "IC11") (pin "9") (pinfunction "UART_RX_9") (pintype "input"))
    )
    (net (code "84") (name "Net-(IC11-UART_TX)") (class "Default")
      (node (ref "FR36") (pin "2") (pinfunction "2_2") (pintype "passive"))
      (node (ref "IC11") (pin "10") (pinfunction "UART_TX_10") (pintype "output"))
    )
    (net (code "85") (name "Net-(J2-X)") (class "Default")
      (node (ref "ESD5") (pin "1") (pinfunction "1_1") (pintype "passive"))
      (node (ref "J2") (pin "1") (pinfunction "X_1") (pintype "passive"))
      (node (ref "R229") (pin "2") (pinfunction "2_2") (pintype "passive"))
      (node (ref "R230") (pin "2") (pinfunction "2_2") (pintype "passive"))
      (node (ref "R231") (pin "2") (pinfunction "2_2") (pintype "passive"))
      (node (ref "R232") (pin "2") (pinfunction "2_2") (pintype "passive"))
    )
    (net (code "86") (name "Net-(LED1-C)") (class "Default")
      (node (ref "LED1") (pin "K") (pinfunction "C_K") (pintype "power_in"))
      (node (ref "R137") (pin "1") (pinfunction "1_1") (pintype "passive"))
    )
    (net (code "87") (name "Net-(LED2-C)") (class "Default")
      (node (ref "LED2") (pin "K") (pinfunction "C_K") (pintype "power_in"))
      (node (ref "R142") (pin "1") (pinfunction "1_1") (pintype "passive"))
    )
    (net (code "88") (name "Net-(R141-Pad2)") (class "Default")
      (node (ref "R141") (pin "2") (pinfunction "2_2") (pintype "passive"))
      (node (ref "X8") (pin "37") (pinfunction "Reserved_37") (pintype "passive"))
    )
    (net (code "89") (name "Net-(R143-Pad2)") (class "Default")
      (node (ref "R143") (pin "2") (pinfunction "2_2") (pintype "passive"))
      (node (ref "X8") (pin "43") (pinfunction "Reserved_43") (pintype "passive"))
    )
    (net (code "90") (name "Net-(R144-Pad2)") (class "Default")
      (node (ref "R144") (pin "2") (pinfunction "2_2") (pintype "passive"))
      (node (ref "X8") (pin "45") (pinfunction "Reserved_45") (pintype "passive"))
    )
    (net (code "91") (name "Net-(X8-SMB_CLK)") (class "Default")
      (node (ref "R136") (pin "1") (pinfunction "1_1") (pintype "passive"))
      (node (ref "R140") (pin "1") (pinfunction "1_1") (pintype "passive"))
      (node (ref "X8") (pin "30") (pinfunction "SMB_CLK_30") (pintype "passive"))
    )
    (net (code "92") (name "Net-(X8-SMB_DATA)") (class "Default")
      (node (ref "R139") (pin "1") (pinfunction "1_1") (pintype "passive"))
      (node (ref "X8") (pin "32") (pinfunction "SMB_DATA_32") (pintype "passive"))
    )
    (net (code "93") (name "VCC1P8") (class "Default")
      (node (ref "C161") (pin "2") (pinfunction "2_2") (pintype "passive"))
      (node (ref "C163") (pin "2") (pinfunction "2_2") (pintype "passive"))
      (node (ref "C170") (pin "2") (pinfunction "2_2") (pintype "passive"))
      (node (ref "C172") (pin "2") (pinfunction "2_2") (pintype "passive"))
      (node (ref "IC10") (pin "14") (pinfunction "VCCA_14") (pintype "passive"))
      (node (ref "IC10") (pin "15") (pinfunction "DIR1_15") (pintype "passive"))
      (node (ref "IC10") (pin "5") (pinfunction "DIR3_5") (pintype "passive"))
      (node (ref "IC10") (pin "6") (pinfunction "DIR4_6") (pintype "passive"))
      (node (ref "IC12") (pin "14") (pinfunction "VCCA_14") (pintype "passive"))
      (node (ref "IC12") (pin "15") (pinfunction "DIR1_15") (pintype "passive"))
      (node (ref "IC12") (pin "16") (pinfunction "DIR2_16") (pintype "passive"))
      (node (ref "IC12") (pin "6") (pinfunction "DIR4_6") (pintype "passive"))
      (node (ref "IC13") (pin "14") (pinfunction "VCCA_14") (pintype "passive"))
      (node (ref "IC13") (pin "15") (pinfunction "DIR1_15") (pintype "passive"))
      (node (ref "IC13") (pin "16") (pinfunction "DIR2_16") (pintype "passive"))
      (node (ref "IC13") (pin "5") (pinfunction "DIR3_5") (pintype "passive"))
      (node (ref "IC13") (pin "6") (pinfunction "DIR4_6") (pintype "passive"))
      (node (ref "IC8") (pin "14") (pinfunction "VCCA_14") (pintype "passive"))
      (node (ref "IC8") (pin "15") (pinfunction "DIR1_15") (pintype "passive"))
      (node (ref "IC8") (pin "5") (pinfunction "DIR3_5") (pintype "passive"))
      (node (ref "JP1") (pin "2") (pinfunction "2_2") (pintype "passive"))
      (node (ref "R110") (pin "1") (pinfunction "1_1") (pintype "passive"))
      (node (ref "R111") (pin "1") (pinfunction "1_1") (pintype "passive"))
      (node (ref "R112") (pin "1") (pinfunction "1_1") (pintype "passive"))
      (node (ref "R113") (pin "1") (pinfunction "1_1") (pintype "passive"))
      (node (ref "R114") (pin "1") (pinfunction "1_1") (pintype "passive"))
      (node (ref "R115") (pin "1") (pinfunction "1_1") (pintype "passive"))
      (node (ref "R116") (pin "1") (pinfunction "1_1") (pintype "passive"))
      (node (ref "R117") (pin "1") (pinfunction "1_1") (pintype "passive"))
      (node (ref "R118") (pin "1") (pinfunction "1_1") (pintype "passive"))
      (node (ref "R119") (pin "1") (pinfunction "1_1") (pintype "passive"))
    )
    (net (code "94") (name "VCC3P3") (class "Default")
      (node (ref "C162") (pin "1") (pinfunction "1_1") (pintype "passive"))
      (node (ref "C164") (pin "1") (pinfunction "1_1") (pintype "passive"))
      (node (ref "C166") (pin "1") (pinfunction "1_1") (pintype "passive"))
      (node (ref "C171") (pin "1") (pinfunction "1_1") (pintype "passive"))
      (node (ref "C173") (pin "1") (pinfunction "1_1") (pintype "passive"))
      (node (ref "C177") (pin "1") (pinfunction "1_1") (pintype "passive"))
      (node (ref "C179") (pin "1") (pinfunction "1_1") (pintype "passive"))
      (node (ref "C180") (pin "1") (pinfunction "1_1") (pintype "passive"))
      (node (ref "FR37") (pin "1") (pinfunction "1_1") (pintype "passive"))
      (node (ref "IC10") (pin "13") (pinfunction "VCCB_13") (pintype "passive"))
      (node (ref "IC12") (pin "13") (pinfunction "VCCB_13") (pintype "passive"))
      (node (ref "IC13") (pin "13") (pinfunction "VCCB_13") (pintype "passive"))
      (node (ref "IC14") (pin "8") (pinfunction "VCC_8") (pintype "power_in"))
      (node (ref "IC15") (pin "5") (pinfunction "VDD_5") (pintype "power_in"))
      (node (ref "IC16") (pin "8") (pinfunction "VCC_8") (pintype "power_in"))
      (node (ref "IC8") (pin "13") (pinfunction "VCCB_13") (pintype "passive"))
      (node (ref "IC9") (pin "5") (pinfunction "V+_5") (pintype "power_in"))
      (node (ref "LED1") (pin "A") (pinfunction "A_A") (pintype "power_in"))
      (node (ref "LED2") (pin "A") (pinfunction "A_A") (pintype "power_in"))
      (node (ref "R130") (pin "1") (pinfunction "1_1") (pintype "passive"))
      (node (ref "X7") (pin "1") (pinfunction "1_1") (pintype "passive"))
    )
    (net (code "95") (name "VCC3P3_GNSS") (class "Default")
      (node (ref "C175") (pin "2") (pinfunction "2_2") (pintype "passive"))
      (node (ref "C176") (pin "2") (pinfunction "2_2") (pintype "passive"))
      (node (ref "FR37") (pin "2") (pinfunction "2_2") (pintype "passive"))
      (node (ref "IC11") (pin "14") (pinfunction "BV_14") (pintype "power_in"))
      (node (ref "IC11") (pin "15") (pinfunction "VCC_15") (pintype "power_in"))
      (node (ref "R108") (pin "2") (pinfunction "2_2") (pintype "passive"))
    )
    (net (code "96") (name "VCC3P3_MPCIE") (class "Default")
      (node (ref "R145") (pin "2") (pinfunction "2_2") (pintype "passive"))
      (node (ref "X8") (pin "2") (pinfunction "+3.3V_2") (pintype "passive"))
      (node (ref "X8") (pin "52") (pinfunction "+3.3V_52") (pintype "passive"))
    )
    (net (code "97") (name "unconnected-(IC9-ALERT-Pad3)") (class "Default")
      (node (ref "IC9") (pin "3") (pinfunction "ALERT_3") (pintype "output+no_connect"))
    )
    (net (code "98") (name "unconnected-(IC11-E2-Pad11)") (class "Default")
      (node (ref "IC11") (pin "11") (pinfunction "E2_11") (pintype "passive+no_connect"))
    )
    (net (code "99") (name "unconnected-(IC11-E3-Pad12)") (class "Default")
      (node (ref "IC11") (pin "12") (pinfunction "E3_12") (pintype "passive+no_connect"))
    )
    (net (code "100") (name "unconnected-(IC15-GPB6-Pad3)") (class "Default")
      (node (ref "IC15") (pin "3") (pinfunction "GPB6_3") (pintype "bidirectional+no_connect"))
    )
    (net (code "101") (name "unconnected-(IC15-INTA-Pad16)") (class "Default")
      (node (ref "IC15") (pin "16") (pinfunction "INTA_16") (pintype "open_collector+no_connect"))
    )
    (net (code "102") (name "unconnected-(IC15-INTB-Pad15)") (class "Default")
      (node (ref "IC15") (pin "15") (pinfunction "INTB_15") (pintype "open_collector+no_connect"))
    )
    (net (code "103") (name "unconnected-(IC15-NC-Pad7)") (class "Default")
      (node (ref "IC15") (pin "7") (pinfunction "NC_7") (pintype "passive+no_connect"))
    )
    (net (code "104") (name "unconnected-(IC15-NC-Pad10)") (class "Default")
      (node (ref "IC15") (pin "10") (pinfunction "NC_10") (pintype "passive+no_connect"))
    )
    (net (code "105") (name "unconnected-(IC16-NC-Pad1)") (class "Default")
      (node (ref "IC16") (pin "1") (pinfunction "NC_1") (pintype "passive+no_connect"))
    )
    (net (code "106") (name "unconnected-(IC16-NC-Pad2)") (class "Default")
      (node (ref "IC16") (pin "2") (pinfunction "NC_2") (pintype "passive+no_connect"))
    )
    (net (code "107") (name "unconnected-(IC16-NC-Pad3)") (class "Default")
      (node (ref "IC16") (pin "3") (pinfunction "NC_3") (pintype "passive+no_connect"))
    )
    (net (code "108") (name "unconnected-(IC16-NC-Pad7)") (class "Default")
      (node (ref "IC16") (pin "7") (pinfunction "NC_7") (pintype "passive+no_connect"))
    )
    (net (code "109") (name "unconnected-(JMP1-Pad1)") (class "Default")
      (node (ref "JMP1") (pin "1") (pinfunction "1_1") (pintype "passive"))
    )
    (net (code "110") (name "unconnected-(JMP1-Pad2)") (class "Default")
      (node (ref "JMP1") (pin "2") (pinfunction "2_2") (pintype "passive"))
    )
    (net (code "111") (name "unconnected-(X8-+1.5V-Pad6)") (class "Default")
      (node (ref "X8") (pin "6") (pinfunction "+1.5V_6") (pintype "passive+no_connect"))
    )
    (net (code "112") (name "unconnected-(X8-+1.5V-Pad28)") (class "Default")
      (node (ref "X8") (pin "28") (pinfunction "+1.5V_28") (pintype "passive+no_connect"))
    )
    (net (code "113") (name "unconnected-(X8-+1.5V-Pad48)") (class "Default")
      (node (ref "X8") (pin "48") (pinfunction "+1.5V_48") (pintype "passive+no_connect"))
    )
    (net (code "114") (name "unconnected-(X8-+3.3Vaux-Pad24)") (class "Default")
      (node (ref "X8") (pin "24") (pinfunction "+3.3Vaux_24") (pintype "passive+no_connect"))
    )
    (net (code "115") (name "unconnected-(X8-UIM_CLK-Pad12)") (class "Default")
      (node (ref "X8") (pin "12") (pinfunction "UIM_CLK_12") (pintype "passive+no_connect"))
    )
    (net (code "116") (name "unconnected-(X8-UIM_DATA-Pad10)") (class "Default")
      (node (ref "X8") (pin "10") (pinfunction "UIM_DATA_10") (pintype "passive+no_connect"))
    )
    (net (code "117") (name "unconnected-(X8-UIM_PWR-Pad8)") (class "Default")
      (node (ref "X8") (pin "8") (pinfunction "UIM_PWR_8") (pintype "passive+no_connect"))
    )
    (net (code "118") (name "unconnected-(X8-UIM_RESET-Pad14)") (class "Default")
      (node (ref "X8") (pin "14") (pinfunction "UIM_RESET_14") (pintype "passive+no_connect"))
    )
    (net (code "119") (name "unconnected-(X8-UIM_VPP-Pad16)") (class "Default")
      (node (ref "X8") (pin "16") (pinfunction "UIM_VPP_16") (pintype "passive+no_connect"))
    )
    (net (code "120") (name "unconnected-(X8-USB_DM-Pad36)") (class "Default")
      (node (ref "X8") (pin "36") (pinfunction "USB_DM_36") (pintype "passive+no_connect"))
    )
    (net (code "121") (name "unconnected-(X8-USB_DP-Pad38)") (class "Default")
      (node (ref "X8") (pin "38") (pinfunction "USB_DP_38") (pintype "passive+no_connect"))
    )
    (net (code "122") (name "unconnected-(X8-WAKE#-Pad1)") (class "Default")
      (node (ref "X8") (pin "1") (pinfunction "WAKE#_1") (pintype "passive+no_connect"))
    )
  )
)
